# DN7C3CA006.net
KiCad netlist of a schematic drawn in EAGLE
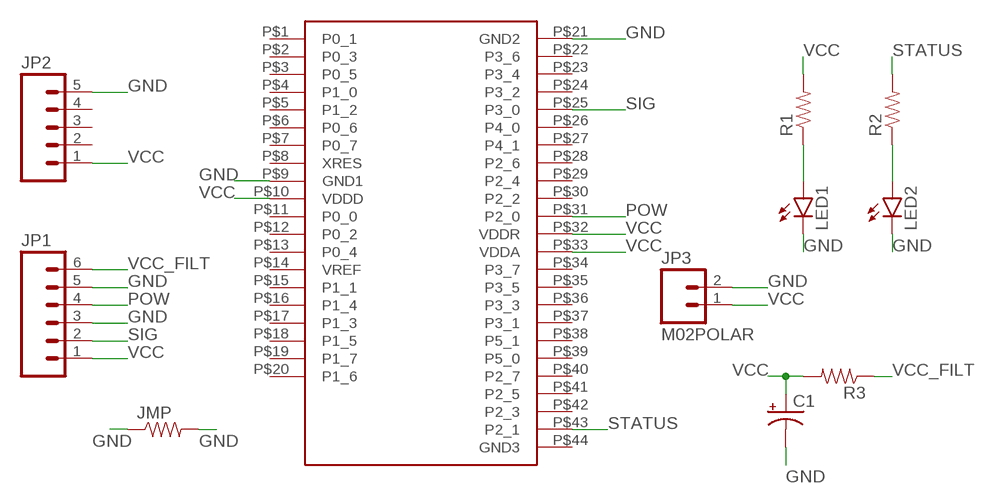
[diagram p0: schematic, sheet 1]

(export (version "E")
  (design (tool "Eeschema 10.0.6"))
  (components
    (comp (ref "C1")
      (value "CAP_POLPTH1")
      (footprint "eagle-import:CPOL-RADIAL-100UF-25V")
      (libsource (lib "eagle-import") (part "CAP_POLPTH1"))
    )
    (comp (ref "JMP")
      (value "RESISTORKIT")
      (footprint "eagle-import:AXIAL-0.3-KIT")
      (libsource (lib "eagle-import") (part "RESISTORKIT"))
    )
    (comp (ref "JP1")
      (value "M06LONGPADS")
      (footprint "eagle-import:1X06_LONGPADS")
      (libsource (lib "eagle-import") (part "M06LONGPADS"))
    )
    (comp (ref "JP2")
      (value "M05PTH_LONGPADS")
      (footprint "eagle-import:1X05_LONGPADS")
      (libsource (lib "eagle-import") (part "M05PTH_LONGPADS"))
    )
    (comp (ref "JP3")
      (value "M02POLAR")
      (footprint "eagle-import:MOLEX-1X2")
      (libsource (lib "eagle-import") (part "M02POLAR"))
    )
    (comp (ref "LED1")
      (value "LED3MM")
      (footprint "eagle-import:LED3MM")
      (libsource (lib "eagle-import") (part "LED3MM"))
    )
    (comp (ref "LED2")
      (value "LED3MM")
      (footprint "eagle-import:LED3MM")
      (libsource (lib "eagle-import") (part "LED3MM"))
    )
    (comp (ref "R1")
      (value "RESISTORPTH-1/4W")
      (footprint "eagle-import:AXIAL-0.4")
      (libsource (lib "eagle-import") (part "RESISTORPTH-1/4W"))
    )
    (comp (ref "R2")
      (value "RESISTORPTH-1/4W")
      (footprint "eagle-import:AXIAL-0.4")
      (libsource (lib "eagle-import") (part "RESISTORPTH-1/4W"))
    )
    (comp (ref "R3")
      (value "RESISTORPTH-1/4W")
      (footprint "eagle-import:AXIAL-0.4")
      (libsource (lib "eagle-import") (part "RESISTORPTH-1/4W"))
    )
    (comp (ref "U$1")
      (value "CYBLE_MODULE")
      (footprint "eagle-import:CYBLE_MODULE")
      (libsource (lib "eagle-import") (part "CYBLE_MODULE"))
    )
  )
  (nets
    (net (code "1") (name "/GND") (class "Default")
      (node (ref "C1") (pin "2") (pinfunction "-_2") (pintype "passive"))
      (node (ref "JMP") (pin "P$1") (pinfunction "1_P$1") (pintype "passive"))
      (node (ref "JMP") (pin "P$2") (pinfunction "2_P$2") (pintype "passive"))
      (node (ref "JP1") (pin "3") (pinfunction "3_3") (pintype "passive"))
      (node (ref "JP1") (pin "5") (pinfunction "5_5") (pintype "passive"))
      (node (ref "JP2") (pin "5") (pinfunction "5_5") (pintype "passive"))
      (node (ref "JP3") (pin "2") (pinfunction "2_2") (pintype "passive"))
      (node (ref "LED1") (pin "K") (pinfunction "C_K") (pintype "passive"))
      (node (ref "LED2") (pin "K") (pinfunction "C_K") (pintype "passive"))
      (node (ref "U$1") (pin "P$21") (pinfunction "GND2_P$21") (pintype "bidirectional"))
      (node (ref "U$1") (pin "P$9") (pinfunction "GND1_P$9") (pintype "bidirectional"))
    )
    (net (code "2") (name "/POW") (class "Default")
      (node (ref "JP1") (pin "4") (pinfunction "4_4") (pintype "passive"))
      (node (ref "U$1") (pin "P$31") (pinfunction "P2_0_P$31") (pintype "bidirectional"))
    )
    (net (code "3") (name "/SIG") (class "Default")
      (node (ref "JP1") (pin "2") (pinfunction "2_2") (pintype "passive"))
      (node (ref "U$1") (pin "P$25") (pinfunction "P3_0_P$25") (pintype "bidirectional"))
    )
    (net (code "4") (name "/STATUS") (class "Default")
      (node (ref "R2") (pin "P$2") (pinfunction "2_P$2") (pintype "passive"))
      (node (ref "U$1") (pin "P$43") (pinfunction "P2_1_P$43") (pintype "bidirectional"))
    )
    (net (code "5") (name "/VCC") (class "Default")
      (node (ref "C1") (pin "1") (pinfunction "+_1") (pintype "passive"))
      (node (ref "JP1") (pin "1") (pinfunction "1_1") (pintype "passive"))
      (node (ref "JP2") (pin "1") (pinfunction "1_1") (pintype "passive"))
      (node (ref "JP3") (pin "1") (pinfunction "1_1") (pintype "passive"))
      (node (ref "R1") (pin "P$2") (pinfunction "2_P$2") (pintype "passive"))
      (node (ref "R3") (pin "P$2") (pinfunction "2_P$2") (pintype "passive"))
      (node (ref "U$1") (pin "P$10") (pinfunction "VDDD_P$10") (pintype "bidirectional"))
      (node (ref "U$1") (pin "P$32") (pinfunction "VDDR_P$32") (pintype "bidirectional"))
      (node (ref "U$1") (pin "P$33") (pinfunction "VDDA_P$33") (pintype "bidirectional"))
    )
    (net (code "6") (name "/VCC_FILT") (class "Default")
      (node (ref "JP1") (pin "6") (pinfunction "6_6") (pintype "passive"))
      (node (ref "R3") (pin "P$1") (pinfunction "1_P$1") (pintype "passive"))
    )
    (net (code "7") (name "Net-(R1-1)") (class "Default")
      (node (ref "LED1") (pin "A") (pinfunction "A_A") (pintype "passive"))
      (node (ref "R1") (pin "P$1") (pinfunction "1_P$1") (pintype "passive"))
    )
    (net (code "8") (name "Net-(R2-1)") (class "Default")
      (node (ref "LED2") (pin "A") (pinfunction "A_A") (pintype "passive"))
      (node (ref "R2") (pin "P$1") (pinfunction "1_P$1") (pintype "passive"))
    )
    (net (code "9") (name "unconnected-(JP2-Pad2)") (class "Default")
      (node (ref "JP2") (pin "2") (pinfunction "2_2") (pintype "passive"))
    )
    (net (code "10") (name "unconnected-(JP2-Pad3)") (class "Default")
      (node (ref "JP2") (pin "3") (pinfunction "3_3") (pintype "passive"))
    )
    (net (code "11") (name "unconnected-(JP2-Pad4)") (class "Default")
      (node (ref "JP2") (pin "4") (pinfunction "4_4") (pintype "passive"))
    )
    (net (code "12") (name "unconnected-(U$1-GND3-PadP$44)") (class "Default")
      (node (ref "U$1") (pin "P$44") (pinfunction "GND3_P$44") (pintype "bidirectional"))
    )
    (net (code "13") (name "unconnected-(U$1-P0_0-PadP$11)") (class "Default")
      (node (ref "U$1") (pin "P$11") (pinfunction "P0_0_P$11") (pintype "bidirectional"))
    )
    (net (code "14") (name "unconnected-(U$1-P0_1-PadP$1)") (class "Default")
      (node (ref "U$1") (pin "P$1") (pinfunction "P0_1_P$1") (pintype "bidirectional"))
    )
    (net (code "15") (name "unconnected-(U$1-P0_2-PadP$12)") (class "Default")
      (node (ref "U$1") (pin "P$12") (pinfunction "P0_2_P$12") (pintype "bidirectional"))
    )
    (net (code "16") (name "unconnected-(U$1-P0_3-PadP$2)") (class "Default")
      (node (ref "U$1") (pin "P$2") (pinfunction "P0_3_P$2") (pintype "bidirectional"))
    )
    (net (code "17") (name "unconnected-(U$1-P0_4-PadP$13)") (class "Default")
      (node (ref "U$1") (pin "P$13") (pinfunction "P0_4_P$13") (pintype "bidirectional"))
    )
    (net (code "18") (name "unconnected-(U$1-P0_5-PadP$3)") (class "Default")
      (node (ref "U$1") (pin "P$3") (pinfunction "P0_5_P$3") (pintype "bidirectional"))
    )
    (net (code "19") (name "unconnected-(U$1-P0_6-PadP$6)") (class "Default")
      (node (ref "U$1") (pin "P$6") (pinfunction "P0_6_P$6") (pintype "bidirectional"))
    )
    (net (code "20") (name "unconnected-(U$1-P0_7-PadP$7)") (class "Default")
      (node (ref "U$1") (pin "P$7") (pinfunction "P0_7_P$7") (pintype "bidirectional"))
    )
    (net (code "21") (name "unconnected-(U$1-P1_0-PadP$4)") (class "Default")
      (node (ref "U$1") (pin "P$4") (pinfunction "P1_0_P$4") (pintype "bidirectional"))
    )
    (net (code "22") (name "unconnected-(U$1-P1_1-PadP$15)") (class "Default")
      (node (ref "U$1") (pin "P$15") (pinfunction "P1_1_P$15") (pintype "bidirectional"))
    )
    (net (code "23") (name "unconnected-(U$1-P1_2-PadP$5)") (class "Default")
      (node (ref "U$1") (pin "P$5") (pinfunction "P1_2_P$5") (pintype "bidirectional"))
    )
    (net (code "24") (name "unconnected-(U$1-P1_3-PadP$17)") (class "Default")
      (node (ref "U$1") (pin "P$17") (pinfunction "P1_3_P$17") (pintype "bidirectional"))
    )
    (net (code "25") (name "unconnected-(U$1-P1_4-PadP$16)") (class "Default")
      (node (ref "U$1") (pin "P$16") (pinfunction "P1_4_P$16") (pintype "bidirectional"))
    )
    (net (code "26") (name "unconnected-(U$1-P1_5-PadP$18)") (class "Default")
      (node (ref "U$1") (pin "P$18") (pinfunction "P1_5_P$18") (pintype "bidirectional"))
    )
    (net (code "27") (name "unconnected-(U$1-P1_6-PadP$20)") (class "Default")
      (node (ref "U$1") (pin "P$20") (pinfunction "P1_6_P$20") (pintype "bidirectional"))
    )
    (net (code "28") (name "unconnected-(U$1-P1_7-PadP$19)") (class "Default")
      (node (ref "U$1") (pin "P$19") (pinfunction "P1_7_P$19") (pintype "bidirectional"))
    )
    (net (code "29") (name "unconnected-(U$1-P2_2-PadP$30)") (class "Default")
      (node (ref "U$1") (pin "P$30") (pinfunction "P2_2_P$30") (pintype "bidirectional"))
    )
    (net (code "30") (name "unconnected-(U$1-P2_3-PadP$42)") (class "Default")
      (node (ref "U$1") (pin "P$42") (pinfunction "P2_3_P$42") (pintype "bidirectional"))
    )
    (net (code "31") (name "unconnected-(U$1-P2_4-PadP$29)") (class "Default")
      (node (ref "U$1") (pin "P$29") (pinfunction "P2_4_P$29") (pintype "bidirectional"))
    )
    (net (code "32") (name "unconnected-(U$1-P2_5-PadP$41)") (class "Default")
      (node (ref "U$1") (pin "P$41") (pinfunction "P2_5_P$41") (pintype "bidirectional"))
    )
    (net (code "33") (name "unconnected-(U$1-P2_6-PadP$28)") (class "Default")
      (node (ref "U$1") (pin "P$28") (pinfunction "P2_6_P$28") (pintype "bidirectional"))
    )
    (net (code "34") (name "unconnected-(U$1-P2_7-PadP$40)") (class "Default")
      (node (ref "U$1") (pin "P$40") (pinfunction "P2_7_P$40") (pintype "bidirectional"))
    )
    (net (code "35") (name "unconnected-(U$1-P3_1-PadP$37)") (class "Default")
      (node (ref "U$1") (pin "P$37") (pinfunction "P3_1_P$37") (pintype "bidirectional"))
    )
    (net (code "36") (name "unconnected-(U$1-P3_2-PadP$24)") (class "Default")
      (node (ref "U$1") (pin "P$24") (pinfunction "P3_2_P$24") (pintype "bidirectional"))
    )
    (net (code "37") (name "unconnected-(U$1-P3_3-PadP$36)") (class "Default")
      (node (ref "U$1") (pin "P$36") (pinfunction "P3_3_P$36") (pintype "bidirectional"))
    )
    (net (code "38") (name "unconnected-(U$1-P3_4-PadP$23)") (class "Default")
      (node (ref "U$1") (pin "P$23") (pinfunction "P3_4_P$23") (pintype "bidirectional"))
    )
    (net (code "39") (name "unconnected-(U$1-P3_5-PadP$35)") (class "Default")
      (node (ref "U$1") (pin "P$35") (pinfunction "P3_5_P$35") (pintype "bidirectional"))
    )
    (net (code "40") (name "unconnected-(U$1-P3_6-PadP$22)") (class "Default")
      (node (ref "U$1") (pin "P$22") (pinfunction "P3_6_P$22") (pintype "bidirectional"))
    )
    (net (code "41") (name "unconnected-(U$1-P3_7-PadP$34)") (class "Default")
      (node (ref "U$1") (pin "P$34") (pinfunction "P3_7_P$34") (pintype "bidirectional"))
    )
    (net (code "42") (name "unconnected-(U$1-P4_0-PadP$26)") (class "Default")
      (node (ref "U$1") (pin "P$26") (pinfunction "P4_0_P$26") (pintype "bidirectional"))
    )
    (net (code "43") (name "unconnected-(U$1-P4_1-PadP$27)") (class "Default")
      (node (ref "U$1") (pin "P$27") (pinfunction "P4_1_P$27") (pintype "bidirectional"))
    )
    (net (code "44") (name "unconnected-(U$1-P5_0-PadP$39)") (class "Default")
      (node (ref "U$1") (pin "P$39") (pinfunction "P5_0_P$39") (pintype "bidirectional"))
    )
    (net (code "45") (name "unconnected-(U$1-P5_1-PadP$38)") (class "Default")
      (node (ref "U$1") (pin "P$38") (pinfunction "P5_1_P$38") (pintype "bidirectional"))
    )
    (net (code "46") (name "unconnected-(U$1-VREF-PadP$14)") (class "Default")
      (node (ref "U$1") (pin "P$14") (pinfunction "VREF_P$14") (pintype "bidirectional"))
    )
    (net (code "47") (name "unconnected-(U$1-XRES-PadP$8)") (class "Default")
      (node (ref "U$1") (pin "P$8") (pinfunction "XRES_P$8") (pintype "bidirectional"))
    )
  )
)
